# SH4_-_IMU.net
KiCad netlist of a schematic drawn in Altium Designer
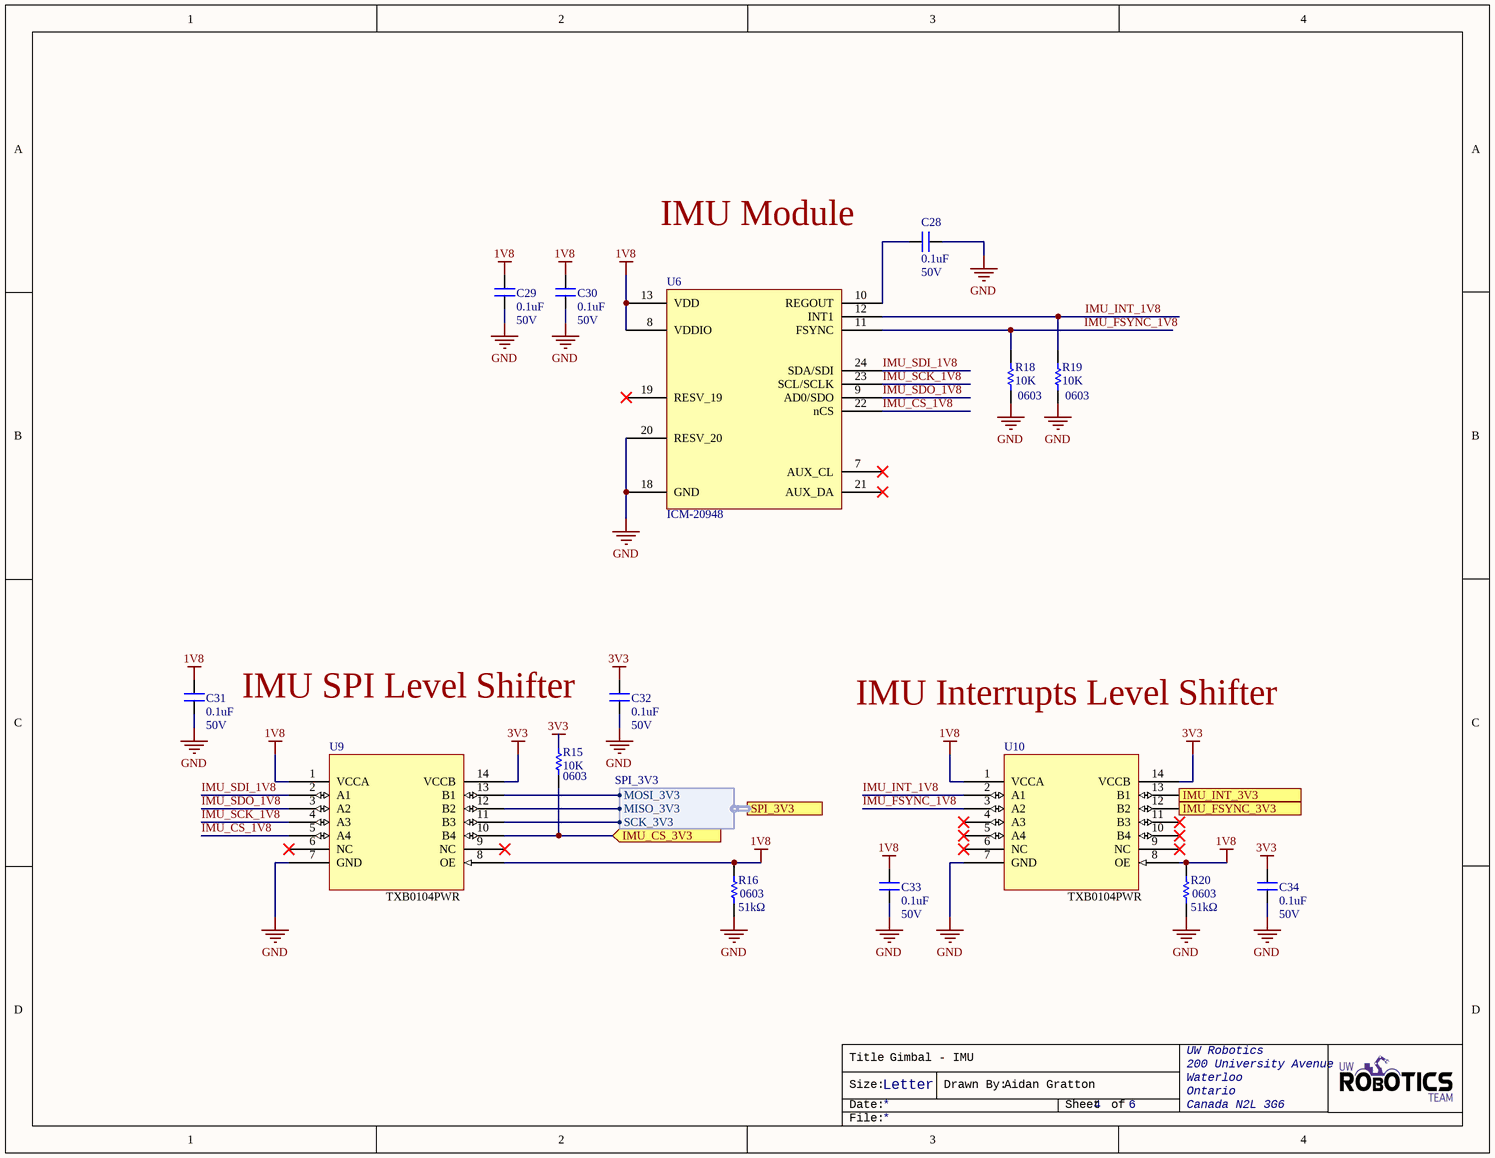
[diagram p0: SH4 - IMU.SchDoc]

(export (version "E")
  (design (tool "Eeschema 10.0.6"))
  (components
    (comp (ref "C28")
      (value "0.1uF")
      (footprint "CAPC2012X140N")
      (description "CAP CER 0.1UF 50V X7R 0805")
      (fields
        (field (name "TOLERANCE") "10%")
        (field (name "VOLTAGE RATING") "50V")
        (field (name "Comment") "CAP_0.1uF_50V_0805")
      )
      (libsource (lib "UWRT_Schematic_Library_2020") (part "CAP_0.1uF_50V_0805"))
    )
    (comp (ref "C29")
      (value "0.1uF")
      (footprint "CAPC2012X140N")
      (description "CAP CER 0.1UF 50V X7R 0805")
      (fields
        (field (name "TOLERANCE") "10%")
        (field (name "VOLTAGE RATING") "50V")
        (field (name "Comment") "CAP_0.1uF_50V_0805")
      )
      (libsource (lib "UWRT_Schematic_Library_2020") (part "CAP_0.1uF_50V_0805"))
    )
    (comp (ref "C30")
      (value "0.1uF")
      (footprint "CAPC2012X140N")
      (description "CAP CER 0.1UF 50V X7R 0805")
      (fields
        (field (name "TOLERANCE") "10%")
        (field (name "VOLTAGE RATING") "50V")
        (field (name "Comment") "CAP_0.1uF_50V_0805")
      )
      (libsource (lib "UWRT_Schematic_Library_2020") (part "CAP_0.1uF_50V_0805"))
    )
    (comp (ref "C31")
      (value "0.1uF")
      (footprint "CAPC2012X140N")
      (description "CAP CER 0.1UF 50V X7R 0805")
      (fields
        (field (name "TOLERANCE") "10%")
        (field (name "VOLTAGE RATING") "50V")
        (field (name "Comment") "CAP_0.1uF_50V_0805")
      )
      (libsource (lib "UWRT_Schematic_Library_2020") (part "CAP_0.1uF_50V_0805"))
    )
    (comp (ref "C32")
      (value "0.1uF")
      (footprint "CAPC2012X140N")
      (description "CAP CER 0.1UF 50V X7R 0805")
      (fields
        (field (name "TOLERANCE") "10%")
        (field (name "VOLTAGE RATING") "50V")
        (field (name "Comment") "CAP_0.1uF_50V_0805")
      )
      (libsource (lib "UWRT_Schematic_Library_2020") (part "CAP_0.1uF_50V_0805"))
    )
    (comp (ref "C33")
      (value "0.1uF")
      (footprint "CAPC2012X140N")
      (description "CAP CER 0.1UF 50V X7R 0805")
      (fields
        (field (name "TOLERANCE") "10%")
        (field (name "VOLTAGE RATING") "50V")
        (field (name "Comment") "CAP_0.1uF_50V_0805")
      )
      (libsource (lib "UWRT_Schematic_Library_2020") (part "CAP_0.1uF_50V_0805"))
    )
    (comp (ref "C34")
      (value "0.1uF")
      (footprint "CAPC2012X140N")
      (description "CAP CER 0.1UF 50V X7R 0805")
      (fields
        (field (name "TOLERANCE") "10%")
        (field (name "VOLTAGE RATING") "50V")
        (field (name "Comment") "CAP_0.1uF_50V_0805")
      )
      (libsource (lib "UWRT_Schematic_Library_2020") (part "CAP_0.1uF_50V_0805"))
    )
    (comp (ref "R15")
      (value "10K")
      (footprint "RESC0603(1608)_N")
      (description "RES SMD 10K OHM 5% 1/10W 0603")
      (fields
        (field (name "PACKAGE") "0603")
        (field (name "MANUFACTURER") "Yageo")
        (field (name "MPN") "RC0603JR-0710KL")
      )
      (libsource (lib "UWRT_Schematic_Library_2020") (part "RES_10K_0603"))
    )
    (comp (ref "R16")
      (value "51kΩ")
      (footprint "UWRT_Footprint_Library_2020:RESC0603(1608)_N")
      (description "RES SMD 51K OHM 5% 1/10W 0603")
      (fields
        (field (name "TOLERANCE") "5%")
        (field (name "CASE CODE (IMPERIAL)") "0603")
        (field (name "Comment") "RES_51kΩ_0603")
      )
      (libsource (lib "UWRT_Schematic_Library_2020") (part "RES_51kΩ_0603"))
    )
    (comp (ref "R18")
      (value "10K")
      (footprint "RESC0603(1608)_N")
      (description "RES SMD 10K OHM 5% 1/10W 0603")
      (fields
        (field (name "PACKAGE") "0603")
        (field (name "TOLERANCE") "5%")
        (field (name "Comment") "RES_10K_0603")
      )
      (libsource (lib "UWRT_Schematic_Library_2020") (part "RES_10K_0603"))
    )
    (comp (ref "R19")
      (value "10K")
      (footprint "RESC0603(1608)_N")
      (description "RES SMD 10K OHM 5% 1/10W 0603")
      (fields
        (field (name "PACKAGE") "0603")
        (field (name "TOLERANCE") "5%")
        (field (name "Comment") "RES_10K_0603")
      )
      (libsource (lib "UWRT_Schematic_Library_2020") (part "RES_10K_0603"))
    )
    (comp (ref "R20")
      (value "51kΩ")
      (footprint "UWRT_Footprint_Library_2020:RESC0603(1608)_N")
      (description "RES SMD 51K OHM 5% 1/10W 0603")
      (fields
        (field (name "TOLERANCE") "5%")
        (field (name "CASE CODE (IMPERIAL)") "0603")
        (field (name "Comment") "RES_51kΩ_0603")
      )
      (libsource (lib "UWRT_Schematic_Library_2020") (part "RES_51kΩ_0603"))
    )
    (comp (ref "U6")
      (value "IC_9DOF_IMU")
      (footprint "ICM-20948")
      (description "IMU ACCEL/GYRO/COMPI2C/SPI 24QFN")
      (fields
        (field (name "MANUFACTURER") "TDK InvenSense")
        (field (name "MANUFACTURER PART NUMBER") "ICM-20948")
      )
      (libsource (lib "UWRT_Schematic_Library_2020") (part "IC_9DOF_IMU"))
    )
    (comp (ref "U9")
      (value "TXB0104PWR")
      (footprint "UWRT_Footprint_Library_2020:PW14")
      (description "IC TRNSLTR BIDIRECTIONAL 14TSSOP")
      (fields
        (field (name "GENERIC_PART_NUMBER") "TXB0104")
        (field (name "MANUFACTURER PART NUMBER 1") "TXB0104PWR")
      )
      (libsource (lib "UWRT_Schematic_Library_2020") (part "IC_4CH_LVL_SHIFTER"))
    )
    (comp (ref "U10")
      (value "TXB0104PWR")
      (footprint "UWRT_Footprint_Library_2020:PW14")
      (description "IC TRNSLTR BIDIRECTIONAL 14TSSOP")
      (fields
        (field (name "GENERIC_PART_NUMBER") "TXB0104")
        (field (name "MANUFACTURER PART NUMBER 1") "TXB0104PWR")
      )
      (libsource (lib "UWRT_Schematic_Library_2020") (part "IC_4CH_LVL_SHIFTER"))
    )
  )
  (nets
    (net (code "2") (name "/IMU_CS_1V8") (class "Default")
      (node (ref "U6") (pin "22") (pinfunction "nCS_22") (pintype "passive"))
      (node (ref "U9") (pin "5") (pinfunction "A4_5") (pintype "bidirectional"))
    )
    (net (code "3") (name "/IMU_CS_3V3") (class "Default")
      (node (ref "R15") (pin "1") (pinfunction "1_1") (pintype "passive"))
      (node (ref "U9") (pin "10") (pinfunction "B4_10") (pintype "bidirectional"))
    )
    (net (code "4") (name "/IMU_FSYNC_1V8") (class "Default")
      (node (ref "R18") (pin "2") (pinfunction "2_2") (pintype "passive"))
      (node (ref "U10") (pin "3") (pinfunction "A2_3") (pintype "bidirectional"))
      (node (ref "U6") (pin "11") (pinfunction "FSYNC_11") (pintype "passive"))
    )
    (net (code "5") (name "/IMU_FSYNC_3V3") (class "Default")
      (node (ref "U10") (pin "12") (pinfunction "B2_12") (pintype "bidirectional"))
    )
    (net (code "6") (name "/IMU_INT_1V8") (class "Default")
      (node (ref "R19") (pin "2") (pinfunction "2_2") (pintype "passive"))
      (node (ref "U10") (pin "2") (pinfunction "A1_2") (pintype "bidirectional"))
      (node (ref "U6") (pin "12") (pinfunction "INT1_12") (pintype "passive"))
    )
    (net (code "7") (name "/IMU_INT_3V3") (class "Default")
      (node (ref "U10") (pin "13") (pinfunction "B1_13") (pintype "bidirectional"))
    )
    (net (code "8") (name "/IMU_SCK_1V8") (class "Default")
      (node (ref "U6") (pin "23") (pinfunction "SCL/SCLK_23") (pintype "passive"))
      (node (ref "U9") (pin "4") (pinfunction "A3_4") (pintype "bidirectional"))
    )
    (net (code "9") (name "/IMU_SDI_1V8") (class "Default")
      (node (ref "U6") (pin "24") (pinfunction "SDA/SDI_24") (pintype "passive"))
      (node (ref "U9") (pin "2") (pinfunction "A1_2") (pintype "bidirectional"))
    )
    (net (code "10") (name "/IMU_SDO_1V8") (class "Default")
      (node (ref "U6") (pin "9") (pinfunction "AD0/SDO_9") (pintype "passive"))
      (node (ref "U9") (pin "3") (pinfunction "A2_3") (pintype "bidirectional"))
    )
    (net (code "11") (name "/MISO_3V3") (class "Default")
      (node (ref "U9") (pin "12") (pinfunction "B2_12") (pintype "bidirectional"))
    )
    (net (code "12") (name "/MOSI_3V3") (class "Default")
      (node (ref "U9") (pin "13") (pinfunction "B1_13") (pintype "bidirectional"))
    )
    (net (code "13") (name "/SCK_3V3") (class "Default")
      (node (ref "U9") (pin "11") (pinfunction "B3_11") (pintype "bidirectional"))
    )
    (net (code "15") (name "1V8") (class "Default")
      (node (ref "C29") (pin "2") (pinfunction "2_2") (pintype "passive"))
      (node (ref "C30") (pin "2") (pinfunction "2_2") (pintype "passive"))
      (node (ref "C31") (pin "2") (pinfunction "2_2") (pintype "passive"))
      (node (ref "C33") (pin "2") (pinfunction "2_2") (pintype "passive"))
      (node (ref "R16") (pin "2") (pinfunction "2_2") (pintype "passive"))
      (node (ref "R20") (pin "2") (pinfunction "2_2") (pintype "passive"))
      (node (ref "U10") (pin "1") (pinfunction "VCCA_1") (pintype "power_in"))
      (node (ref "U10") (pin "8") (pinfunction "OE_8") (pintype "input"))
      (node (ref "U6") (pin "13") (pinfunction "VDD_13") (pintype "passive"))
      (node (ref "U6") (pin "8") (pinfunction "VDDIO_8") (pintype "passive"))
      (node (ref "U9") (pin "1") (pinfunction "VCCA_1") (pintype "power_in"))
      (node (ref "U9") (pin "8") (pinfunction "OE_8") (pintype "input"))
    )
    (net (code "16") (name "3V3") (class "Default")
      (node (ref "C32") (pin "2") (pinfunction "2_2") (pintype "passive"))
      (node (ref "C34") (pin "2") (pinfunction "2_2") (pintype "passive"))
      (node (ref "R15") (pin "2") (pinfunction "2_2") (pintype "passive"))
      (node (ref "U10") (pin "14") (pinfunction "VCCB_14") (pintype "power_in"))
      (node (ref "U9") (pin "14") (pinfunction "VCCB_14") (pintype "power_in"))
    )
    (net (code "17") (name "GND") (class "Default")
      (node (ref "C28") (pin "2") (pinfunction "2_2") (pintype "passive"))
      (node (ref "C29") (pin "1") (pinfunction "1_1") (pintype "passive"))
      (node (ref "C30") (pin "1") (pinfunction "1_1") (pintype "passive"))
      (node (ref "C31") (pin "1") (pinfunction "1_1") (pintype "passive"))
      (node (ref "C32") (pin "1") (pinfunction "1_1") (pintype "passive"))
      (node (ref "C33") (pin "1") (pinfunction "1_1") (pintype "passive"))
      (node (ref "C34") (pin "1") (pinfunction "1_1") (pintype "passive"))
      (node (ref "R16") (pin "1") (pinfunction "1_1") (pintype "passive"))
      (node (ref "R18") (pin "1") (pinfunction "1_1") (pintype "passive"))
      (node (ref "R19") (pin "1") (pinfunction "1_1") (pintype "passive"))
      (node (ref "R20") (pin "1") (pinfunction "1_1") (pintype "passive"))
      (node (ref "U10") (pin "7") (pinfunction "GND_7") (pintype "power_in"))
      (node (ref "U6") (pin "18") (pinfunction "GND_18") (pintype "passive"))
      (node (ref "U6") (pin "20") (pinfunction "RESV_20_20") (pintype "passive"))
      (node (ref "U9") (pin "7") (pinfunction "GND_7") (pintype "power_in"))
    )
    (net (code "18") (name "Net-(U6-REGOUT)") (class "Default")
      (node (ref "C28") (pin "1") (pinfunction "1_1") (pintype "passive"))
      (node (ref "U6") (pin "10") (pinfunction "REGOUT_10") (pintype "passive"))
    )
    (net (code "19") (name "unconnected-(U6-AUX_CL-Pad7)") (class "Default")
      (node (ref "U6") (pin "7") (pinfunction "AUX_CL_7") (pintype "passive+no_connect"))
    )
    (net (code "20") (name "unconnected-(U6-AUX_DA-Pad21)") (class "Default")
      (node (ref "U6") (pin "21") (pinfunction "AUX_DA_21") (pintype "passive+no_connect"))
    )
    (net (code "21") (name "unconnected-(U6-RESV_19-Pad19)") (class "Default")
      (node (ref "U6") (pin "19") (pinfunction "RESV_19_19") (pintype "passive+no_connect"))
    )
    (net (code "22") (name "unconnected-(U9-NC-Pad6)") (class "Default")
      (node (ref "U9") (pin "6") (pinfunction "NC_6") (pintype "passive+no_connect"))
    )
    (net (code "23") (name "unconnected-(U9-NC-Pad9)") (class "Default")
      (node (ref "U9") (pin "9") (pinfunction "NC_9") (pintype "passive+no_connect"))
    )
    (net (code "24") (name "unconnected-(U10-A3-Pad4)") (class "Default")
      (node (ref "U10") (pin "4") (pinfunction "A3_4") (pintype "bidirectional+no_connect"))
    )
    (net (code "25") (name "unconnected-(U10-A4-Pad5)") (class "Default")
      (node (ref "U10") (pin "5") (pinfunction "A4_5") (pintype "bidirectional+no_connect"))
    )
    (net (code "26") (name "unconnected-(U10-B3-Pad11)") (class "Default")
      (node (ref "U10") (pin "11") (pinfunction "B3_11") (pintype "bidirectional+no_connect"))
    )
    (net (code "27") (name "unconnected-(U10-B4-Pad10)") (class "Default")
      (node (ref "U10") (pin "10") (pinfunction "B4_10") (pintype "bidirectional+no_connect"))
    )
    (net (code "28") (name "unconnected-(U10-NC-Pad6)") (class "Default")
      (node (ref "U10") (pin "6") (pinfunction "NC_6") (pintype "passive+no_connect"))
    )
    (net (code "29") (name "unconnected-(U10-NC-Pad9)") (class "Default")
      (node (ref "U10") (pin "9") (pinfunction "NC_9") (pintype "passive+no_connect"))
    )
  )
)
